# PCB-SSB-1x1ENC.net
KiCad netlist of a schematic drawn in EAGLE
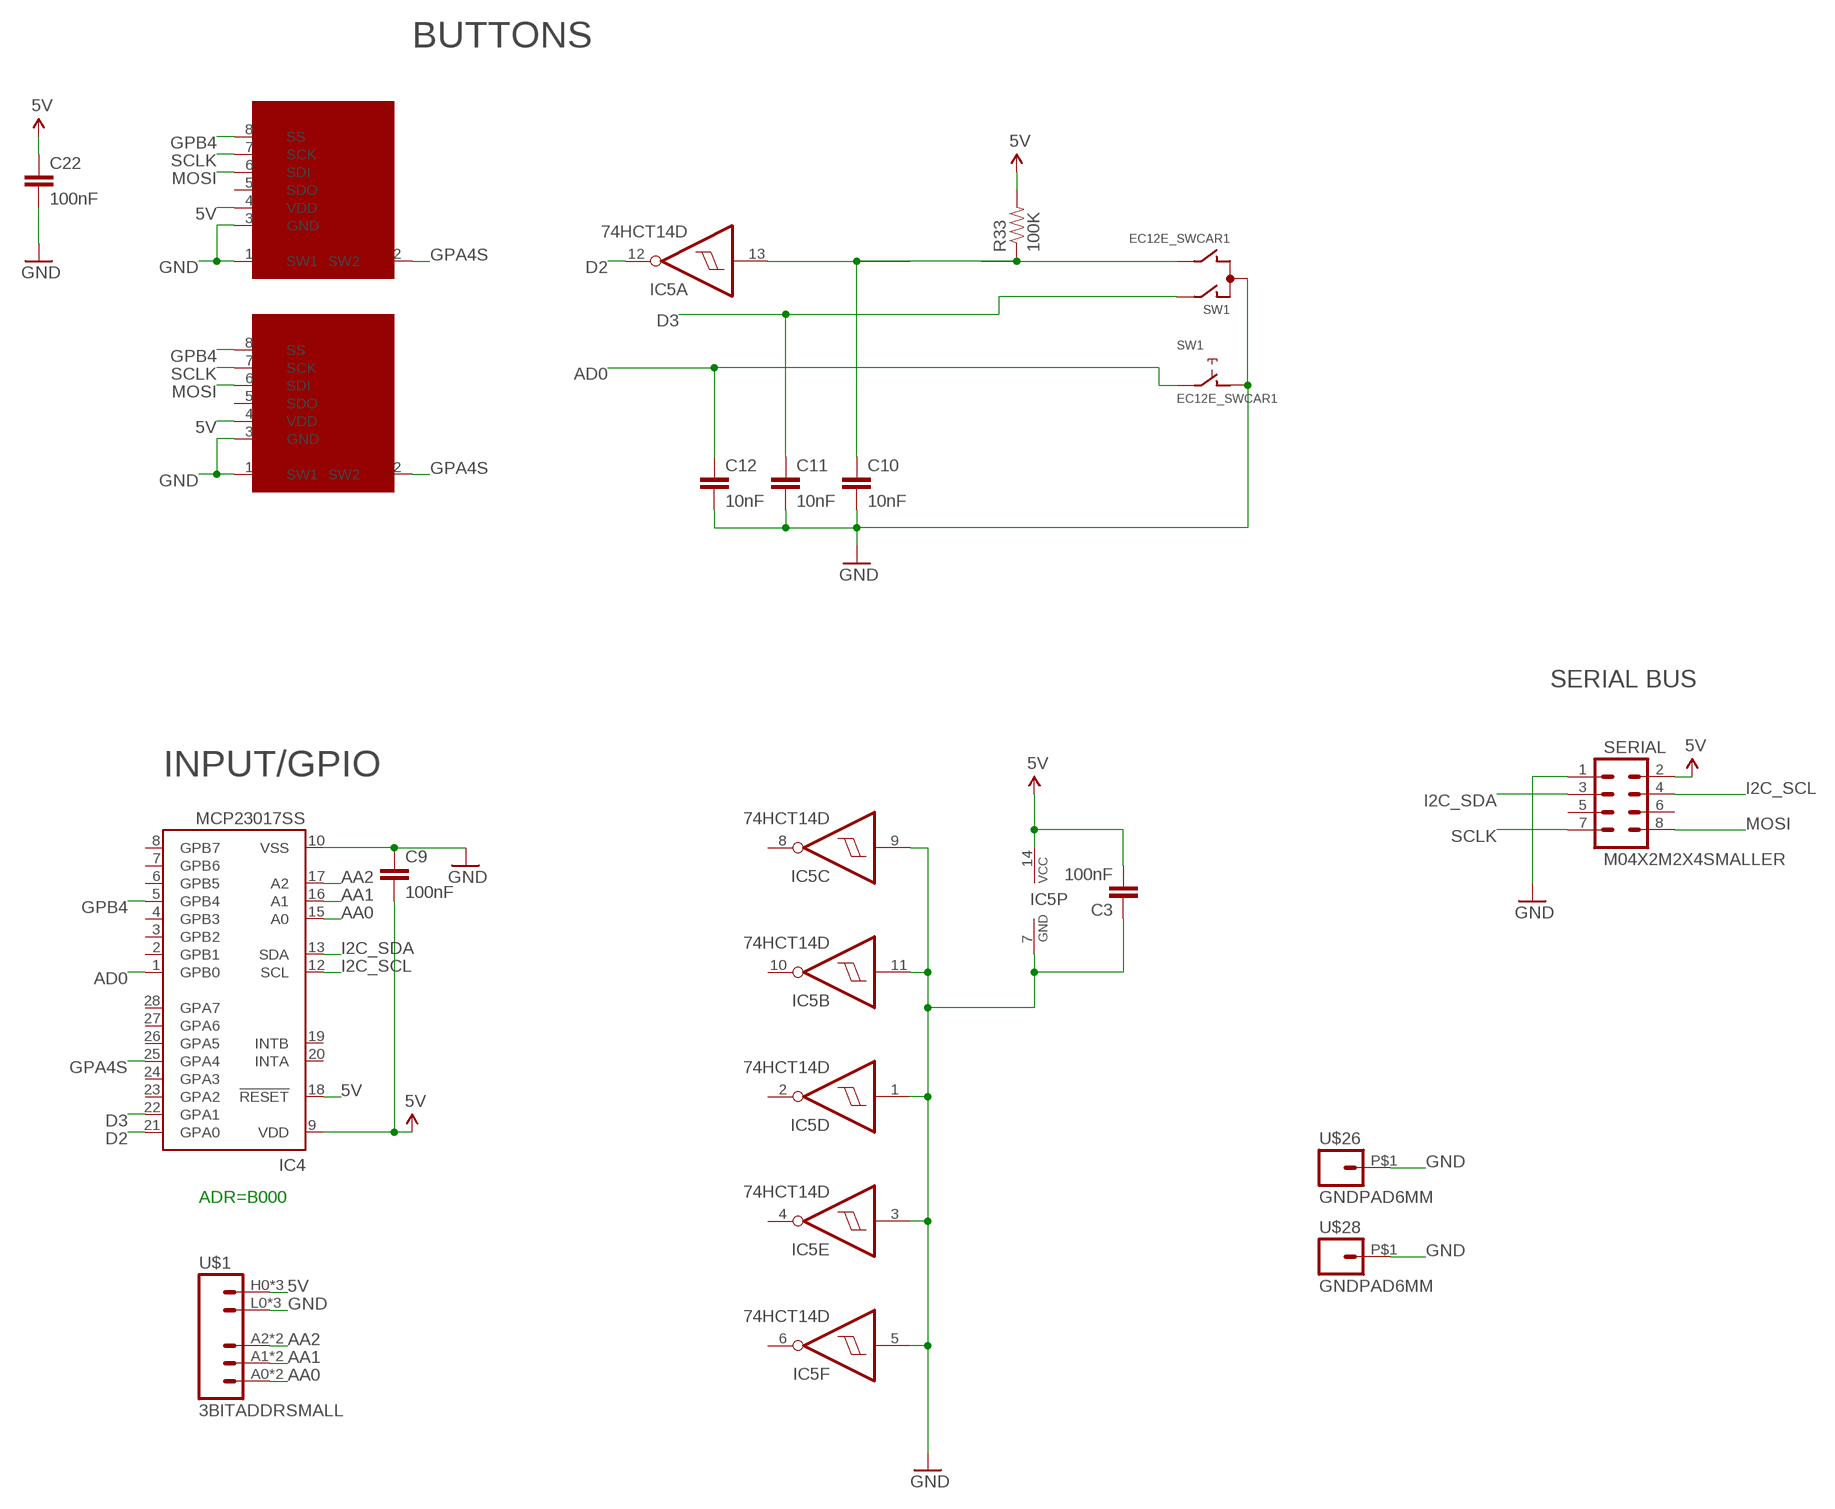
[diagram p0: schematic, sheet 1]

(export (version "E")
  (design (tool "Eeschema 10.0.6"))
  (components
    (comp (ref "C3")
      (value "100nF")
      (footprint "eagle-import:0603-CAP")
      (libsource (lib "eagle-import") (part "CAP0603-CAP"))
    )
    (comp (ref "C9")
      (value "100nF")
      (footprint "eagle-import:0603-CAP")
      (libsource (lib "eagle-import") (part "CAP0603-CAP"))
    )
    (comp (ref "C10")
      (value "10nF")
      (footprint "eagle-import:0603-CAP")
      (libsource (lib "eagle-import") (part "CAP0603-CAP"))
    )
    (comp (ref "C11")
      (value "10nF")
      (footprint "eagle-import:0603-CAP")
      (libsource (lib "eagle-import") (part "CAP0603-CAP"))
    )
    (comp (ref "C12")
      (value "10nF")
      (footprint "eagle-import:0603-CAP")
      (libsource (lib "eagle-import") (part "CAP0603-CAP"))
    )
    (comp (ref "C22")
      (value "100nF")
      (footprint "eagle-import:0603-CAP")
      (libsource (lib "eagle-import") (part "CAP0603-CAP"))
    )
    (comp (ref "IC4")
      (value "MCP23017SS")
      (footprint "eagle-import:SSOP28")
      (fields
        (field (name "MF") "MICROCHIP")
        (field (name "MPN") "MCP23017-E/SS")
        (field (name "MPN_1") "MCP23017-E/SS")
        (field (name "OC_FARNELL") "1467674")
        (field (name "OC_NEWARK") "31K2960")
      )
      (libsource (lib "eagle-import") (part "MCP23017SS"))
    )
    (comp (ref "IC5")
      (value "74HCT14D")
      (footprint "eagle-import:SO14")
      (libsource (lib "eagle-import") (part "7414DHCT"))
    )
    (comp (ref "R33")
      (value "100K")
      (footprint "eagle-import:0603-RES")
      (libsource (lib "eagle-import") (part "RESISTOR0603-RES"))
    )
    (comp (ref "SERIAL")
      (value "M04X2M2X4SMALLER")
      (footprint "eagle-import:M2X4SMALLER")
      (libsource (lib "eagle-import") (part "M04X2M2X4SMALLER"))
    )
    (comp (ref "SSW1")
      (value "SMART_SWITCHSMART_SWITCH_8PIN")
      (footprint "eagle-import:SMART_SWITCH")
      (libsource (lib "eagle-import") (part "SMART_SWITCHSMART_SWITCH_8PIN"))
    )
    (comp (ref "SSW1ALT")
      (value "SMART_SWITCHSMART_SWITCH_8PIN")
      (footprint "eagle-import:SMART_SWITCH")
      (libsource (lib "eagle-import") (part "SMART_SWITCHSMART_SWITCH_8PIN"))
    )
    (comp (ref "SW1")
      (value "EC12E_SWCAR1")
      (footprint "eagle-import:ALPS_EC12E_SW-CAR1")
      (libsource (lib "eagle-import") (part "EC12E_SWCAR1"))
    )
    (comp (ref "U$1")
      (value "3BITADDRSMALL")
      (footprint "eagle-import:3BITADDR_SMALL")
      (libsource (lib "eagle-import") (part "3BITADDRSMALL"))
    )
    (comp (ref "U$26")
      (value "GNDPAD6MM")
      (footprint "eagle-import:3.2MMPAD6MM")
      (libsource (lib "eagle-import") (part "GNDPAD6MM"))
    )
    (comp (ref "U$28")
      (value "GNDPAD6MM")
      (footprint "eagle-import:3.2MMPAD6MM")
      (libsource (lib "eagle-import") (part "GNDPAD6MM"))
    )
  )
  (nets
    (net (code "1") (name "5V") (class "Default")
      (node (ref "C22") (pin "1") (pinfunction "1_1") (pintype "passive"))
      (node (ref "C3") (pin "2") (pinfunction "2_2") (pintype "passive"))
      (node (ref "C9") (pin "2") (pinfunction "2_2") (pintype "passive"))
      (node (ref "IC4") (pin "18") (pinfunction "~{RESET}_18") (pintype "input"))
      (node (ref "IC4") (pin "9") (pinfunction "VDD_9") (pintype "power_in"))
      (node (ref "IC5") (pin "14") (pinfunction "VCC_14") (pintype "power_in"))
      (node (ref "R33") (pin "2") (pinfunction "2_2") (pintype "passive"))
      (node (ref "SERIAL") (pin "2") (pinfunction "2_2") (pintype "passive"))
      (node (ref "SSW1") (pin "4") (pinfunction "VDD_4") (pintype "bidirectional"))
      (node (ref "SSW1ALT") (pin "4") (pinfunction "VDD_4") (pintype "bidirectional"))
      (node (ref "U$1") (pin "H0") (pinfunction "VCC_H0") (pintype "passive"))
      (node (ref "U$1") (pin "H1") (pinfunction "VCC_H1") (pintype "passive"))
      (node (ref "U$1") (pin "H2") (pinfunction "VCC_H2") (pintype "passive"))
    )
    (net (code "2") (name "AA0") (class "Default")
      (node (ref "IC4") (pin "15") (pinfunction "A0_15") (pintype "input"))
      (node (ref "U$1") (pin "A0") (pinfunction "A0_A0") (pintype "passive"))
      (node (ref "U$1") (pin "AS0") (pinfunction "A0_AS0") (pintype "passive"))
    )
    (net (code "3") (name "AA1") (class "Default")
      (node (ref "IC4") (pin "16") (pinfunction "A1_16") (pintype "input"))
      (node (ref "U$1") (pin "A1") (pinfunction "A1_A1") (pintype "passive"))
      (node (ref "U$1") (pin "AS1") (pinfunction "A1_AS1") (pintype "passive"))
    )
    (net (code "4") (name "AA2") (class "Default")
      (node (ref "IC4") (pin "17") (pinfunction "A2_17") (pintype "input"))
      (node (ref "U$1") (pin "A2") (pinfunction "A2_A2") (pintype "passive"))
      (node (ref "U$1") (pin "AS2") (pinfunction "A2_AS2") (pintype "passive"))
    )
    (net (code "5") (name "AD0") (class "Default")
      (node (ref "C12") (pin "1") (pinfunction "1_1") (pintype "passive"))
      (node (ref "IC4") (pin "1") (pinfunction "GPB0_1") (pintype "bidirectional"))
      (node (ref "SW1") (pin "E") (pinfunction "2_E") (pintype "passive"))
    )
    (net (code "6") (name "D2") (class "Default")
      (node (ref "IC4") (pin "21") (pinfunction "GPA0_21") (pintype "bidirectional"))
      (node (ref "IC5") (pin "12") (pinfunction "O_12") (pintype "output"))
    )
    (net (code "7") (name "D3") (class "Default")
      (node (ref "C11") (pin "1") (pinfunction "1_1") (pintype "passive"))
      (node (ref "IC4") (pin "22") (pinfunction "GPA1_22") (pintype "bidirectional"))
      (node (ref "SW1") (pin "A") (pinfunction "A_A") (pintype "passive"))
    )
    (net (code "8") (name "GND") (class "Default")
      (node (ref "C10") (pin "2") (pinfunction "2_2") (pintype "passive"))
      (node (ref "C11") (pin "2") (pinfunction "2_2") (pintype "passive"))
      (node (ref "C12") (pin "2") (pinfunction "2_2") (pintype "passive"))
      (node (ref "C22") (pin "2") (pinfunction "2_2") (pintype "passive"))
      (node (ref "C3") (pin "1") (pinfunction "1_1") (pintype "passive"))
      (node (ref "C9") (pin "1") (pinfunction "1_1") (pintype "passive"))
      (node (ref "IC4") (pin "10") (pinfunction "VSS_10") (pintype "power_in"))
      (node (ref "IC5") (pin "1") (pinfunction "I_1") (pintype "input"))
      (node (ref "IC5") (pin "11") (pinfunction "I_11") (pintype "input"))
      (node (ref "IC5") (pin "3") (pinfunction "I_3") (pintype "input"))
      (node (ref "IC5") (pin "5") (pinfunction "I_5") (pintype "input"))
      (node (ref "IC5") (pin "7") (pinfunction "GND_7") (pintype "power_in"))
      (node (ref "IC5") (pin "9") (pinfunction "I_9") (pintype "input"))
      (node (ref "SERIAL") (pin "1") (pinfunction "1_1") (pintype "passive"))
      (node (ref "SSW1") (pin "1") (pinfunction "SW1_1") (pintype "bidirectional"))
      (node (ref "SSW1") (pin "3") (pinfunction "GND_3") (pintype "bidirectional"))
      (node (ref "SSW1ALT") (pin "1") (pinfunction "SW1_1") (pintype "bidirectional"))
      (node (ref "SSW1ALT") (pin "3") (pinfunction "GND_3") (pintype "bidirectional"))
      (node (ref "SW1") (pin "C") (pinfunction "C_C") (pintype "passive"))
      (node (ref "SW1") (pin "D") (pinfunction "1_D") (pintype "passive"))
      (node (ref "U$1") (pin "L0") (pinfunction "GND_L0") (pintype "passive"))
      (node (ref "U$1") (pin "L1") (pinfunction "GND_L1") (pintype "passive"))
      (node (ref "U$1") (pin "L2") (pinfunction "GND_L2") (pintype "passive"))
      (node (ref "U$26") (pin "P$1") (pinfunction "1_P$1") (pintype "passive"))
      (node (ref "U$28") (pin "P$1") (pinfunction "1_P$1") (pintype "passive"))
    )
    (net (code "9") (name "GPA4S") (class "Default")
      (node (ref "IC4") (pin "25") (pinfunction "GPA4_25") (pintype "bidirectional"))
      (node (ref "SSW1") (pin "2") (pinfunction "SW2_2") (pintype "bidirectional"))
      (node (ref "SSW1ALT") (pin "2") (pinfunction "SW2_2") (pintype "bidirectional"))
    )
    (net (code "10") (name "GPB4") (class "Default")
      (node (ref "IC4") (pin "5") (pinfunction "GPB4_5") (pintype "bidirectional"))
      (node (ref "SSW1") (pin "8") (pinfunction "SS_8") (pintype "bidirectional"))
      (node (ref "SSW1ALT") (pin "8") (pinfunction "SS_8") (pintype "bidirectional"))
    )
    (net (code "11") (name "I2C_SCL") (class "Default")
      (node (ref "IC4") (pin "12") (pinfunction "SCL_12") (pintype "input"))
      (node (ref "SERIAL") (pin "4") (pinfunction "4_4") (pintype "passive"))
    )
    (net (code "12") (name "I2C_SDA") (class "Default")
      (node (ref "IC4") (pin "13") (pinfunction "SDA_13") (pintype "bidirectional"))
      (node (ref "SERIAL") (pin "3") (pinfunction "3_3") (pintype "passive"))
    )
    (net (code "13") (name "MOSI") (class "Default")
      (node (ref "SERIAL") (pin "8") (pinfunction "8_8") (pintype "passive"))
      (node (ref "SSW1") (pin "6") (pinfunction "SDI_6") (pintype "bidirectional"))
      (node (ref "SSW1ALT") (pin "6") (pinfunction "SDI_6") (pintype "bidirectional"))
    )
    (net (code "14") (name "Net-(IC5A-I)") (class "Default")
      (node (ref "C10") (pin "1") (pinfunction "1_1") (pintype "passive"))
      (node (ref "IC5") (pin "13") (pinfunction "I_13") (pintype "input"))
      (node (ref "R33") (pin "1") (pinfunction "1_1") (pintype "passive"))
      (node (ref "SW1") (pin "B") (pinfunction "B_B") (pintype "passive"))
    )
    (net (code "15") (name "SCLK") (class "Default")
      (node (ref "SERIAL") (pin "7") (pinfunction "7_7") (pintype "passive"))
      (node (ref "SSW1") (pin "7") (pinfunction "SCK_7") (pintype "bidirectional"))
      (node (ref "SSW1ALT") (pin "7") (pinfunction "SCK_7") (pintype "bidirectional"))
    )
    (net (code "16") (name "unconnected-(IC4-GPA2-Pad23)") (class "Default")
      (node (ref "IC4") (pin "23") (pinfunction "GPA2_23") (pintype "bidirectional"))
    )
    (net (code "17") (name "unconnected-(IC4-GPA3-Pad24)") (class "Default")
      (node (ref "IC4") (pin "24") (pinfunction "GPA3_24") (pintype "bidirectional"))
    )
    (net (code "18") (name "unconnected-(IC4-GPA5-Pad26)") (class "Default")
      (node (ref "IC4") (pin "26") (pinfunction "GPA5_26") (pintype "bidirectional"))
    )
    (net (code "19") (name "unconnected-(IC4-GPA6-Pad27)") (class "Default")
      (node (ref "IC4") (pin "27") (pinfunction "GPA6_27") (pintype "bidirectional"))
    )
    (net (code "20") (name "unconnected-(IC4-GPA7-Pad28)") (class "Default")
      (node (ref "IC4") (pin "28") (pinfunction "GPA7_28") (pintype "bidirectional"))
    )
    (net (code "21") (name "unconnected-(IC4-GPB1-Pad2)") (class "Default")
      (node (ref "IC4") (pin "2") (pinfunction "GPB1_2") (pintype "bidirectional"))
    )
    (net (code "22") (name "unconnected-(IC4-GPB2-Pad3)") (class "Default")
      (node (ref "IC4") (pin "3") (pinfunction "GPB2_3") (pintype "bidirectional"))
    )
    (net (code "23") (name "unconnected-(IC4-GPB3-Pad4)") (class "Default")
      (node (ref "IC4") (pin "4") (pinfunction "GPB3_4") (pintype "bidirectional"))
    )
    (net (code "24") (name "unconnected-(IC4-GPB5-Pad6)") (class "Default")
      (node (ref "IC4") (pin "6") (pinfunction "GPB5_6") (pintype "bidirectional"))
    )
    (net (code "25") (name "unconnected-(IC4-GPB6-Pad7)") (class "Default")
      (node (ref "IC4") (pin "7") (pinfunction "GPB6_7") (pintype "bidirectional"))
    )
    (net (code "26") (name "unconnected-(IC4-GPB7-Pad8)") (class "Default")
      (node (ref "IC4") (pin "8") (pinfunction "GPB7_8") (pintype "bidirectional"))
    )
    (net (code "27") (name "unconnected-(IC4-INTA-Pad20)") (class "Default")
      (node (ref "IC4") (pin "20") (pinfunction "INTA_20") (pintype "output"))
    )
    (net (code "28") (name "unconnected-(IC4-INTB-Pad19)") (class "Default")
      (node (ref "IC4") (pin "19") (pinfunction "INTB_19") (pintype "output"))
    )
    (net (code "29") (name "unconnected-(IC5B-O-Pad10)") (class "Default")
      (node (ref "IC5") (pin "10") (pinfunction "O_10") (pintype "output"))
    )
    (net (code "30") (name "unconnected-(IC5C-O-Pad8)") (class "Default")
      (node (ref "IC5") (pin "8") (pinfunction "O_8") (pintype "output"))
    )
    (net (code "31") (name "unconnected-(IC5D-O-Pad2)") (class "Default")
      (node (ref "IC5") (pin "2") (pinfunction "O_2") (pintype "output"))
    )
    (net (code "32") (name "unconnected-(IC5E-O-Pad4)") (class "Default")
      (node (ref "IC5") (pin "4") (pinfunction "O_4") (pintype "output"))
    )
    (net (code "33") (name "unconnected-(IC5F-O-Pad6)") (class "Default")
      (node (ref "IC5") (pin "6") (pinfunction "O_6") (pintype "output"))
    )
    (net (code "34") (name "unconnected-(SERIAL-Pad5)") (class "Default")
      (node (ref "SERIAL") (pin "5") (pinfunction "5_5") (pintype "passive"))
    )
    (net (code "35") (name "unconnected-(SERIAL-Pad6)") (class "Default")
      (node (ref "SERIAL") (pin "6") (pinfunction "6_6") (pintype "passive"))
    )
    (net (code "36") (name "unconnected-(SSW1-SDO-Pad5)") (class "Default")
      (node (ref "SSW1") (pin "5") (pinfunction "SDO_5") (pintype "bidirectional"))
    )
    (net (code "37") (name "unconnected-(SSW1ALT-SDO-Pad5)") (class "Default")
      (node (ref "SSW1ALT") (pin "5") (pinfunction "SDO_5") (pintype "bidirectional"))
    )
  )
)
